# UART_USB.net
KiCad netlist of a schematic drawn in Altium Designer
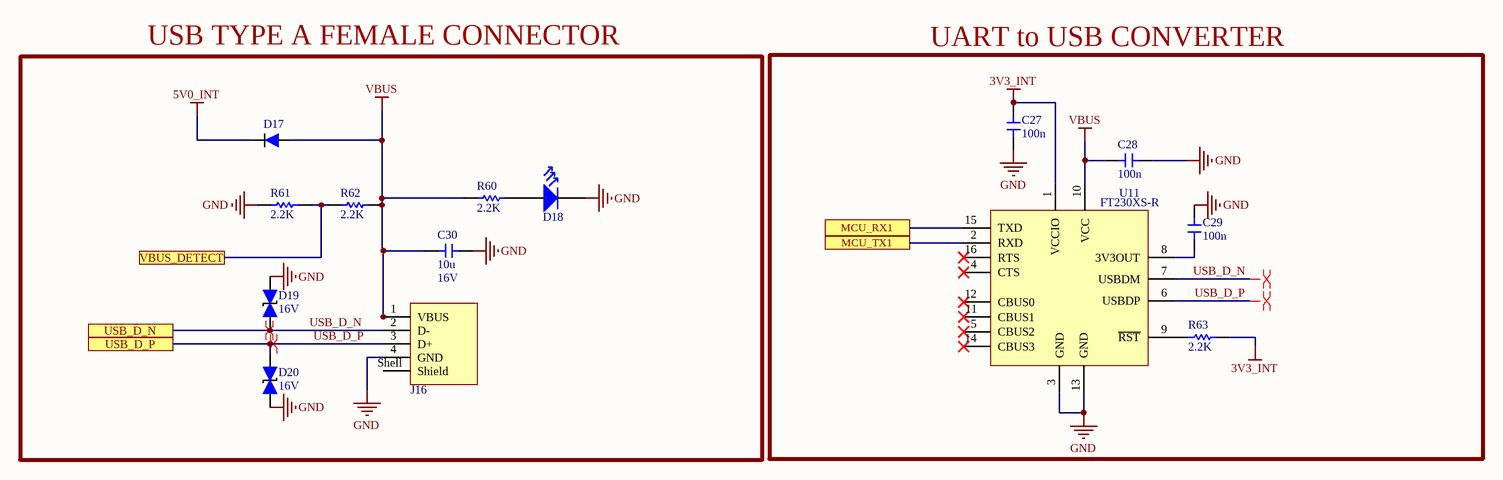
[diagram p0: UART_USB.SchDoc]

(export (version "E")
  (design (tool "Eeschema 10.0.6"))
  (components
    (comp (ref "C27")
      (value "100n")
      (footprint "CAP_0402_CER")
      (description "Generic")
      (fields (field (name "PART NUMBER") "CL05B104KP5NNNC") (field (name "VOLTAGE") "10V"))
      (libsource (lib "MareLux24Lib") (part "CAP_GEN_CER"))
    )
    (comp (ref "C28")
      (value "100n")
      (footprint "CAP_0402_CER")
      (description "Generic")
      (fields (field (name "PART NUMBER") "CL05B104KP5NNNC") (field (name "VOLTAGE") "10V"))
      (libsource (lib "MareLux24Lib") (part "CAP_GEN_CER"))
    )
    (comp (ref "C29")
      (value "100n")
      (footprint "CAP_0402_CER")
      (description "Generic")
      (fields (field (name "PART NUMBER") "CL05B104KP5NNNC") (field (name "VOLTAGE") "10V"))
      (libsource (lib "MareLux24Lib") (part "CAP_GEN_CER"))
    )
    (comp (ref "C30")
      (value "10u")
      (footprint "CAP_0805_CER")
      (description "Generic")
      (fields (field (name "PART NUMBER") "CL21A106KOQNNNE") (field (name "VOLTAGE") "16V"))
      (libsource (lib "MareLux24Lib") (part "CAP_GEN_CER"))
    )
    (comp (ref "D17")
      (value "BAT42WS-E3-08")
      (footprint "SOD323F")
      (description "DIODE SCHOTTKY 30V 200MA")
      (fields (field (name "VOLTAGE") "30V"))
      (libsource (lib "MareLux24Lib") (part "BAT42WS-E3-08"))
    )
    (comp (ref "D18")
      (value "*")
      (footprint "LED_0805_SMD")
      (libsource (lib "MareLux24Lib") (part "LED_GEN"))
    )
    (comp (ref "D19")
      (value "16V")
      (footprint "SOD-123F")
      (description "Unidirectional TVS DIODE 200W 16V-17.8V SOD-123")
      (fields (field (name "PART NUMBER") "SMF16CA") (field (name "VOLTAGE") "17.8V"))
      (libsource (lib "MareLux24Lib") (part "SMF16CA"))
    )
    (comp (ref "D20")
      (value "16V")
      (footprint "SOD-123F")
      (description "Unidirectional TVS DIODE 200W 16V-17.8V SOD-123")
      (fields (field (name "PART NUMBER") "SMF16CA") (field (name "VOLTAGE") "17.8V"))
      (libsource (lib "MareLux24Lib") (part "SMF16CA"))
    )
    (comp (ref "J16")
      (value "UJ2-BH-1-TH")
      (footprint "61400416021")
      (description "WR-COM USB 2.0 Type A Horizontal")
      (fields
        (field (name "MANUFACTURER PART NUMBER") "61400416021")
        (field (name "MANUFACTURER") "Wurth Elektronik")
      )
      (libsource (lib "Altium_WR-USB_rev22b") (part "61400416021"))
    )
    (comp (ref "R60")
      (value "2.2K")
      (footprint "RES_0402_SMD")
      (description "Generic Chip Res")
      (fields (field (name "PART NUMBER") "RMCF0402JT2K20"))
      (libsource (lib "MareLux24Lib") (part "RES_GEN_SMD"))
    )
    (comp (ref "R61")
      (value "2.2K")
      (footprint "RES_0402_SMD")
      (description "Generic Chip Res")
      (fields (field (name "PART NUMBER") "RMCF0402JT2K20"))
      (libsource (lib "MareLux24Lib") (part "RES_GEN_SMD"))
    )
    (comp (ref "R62")
      (value "2.2K")
      (footprint "RES_0402_SMD")
      (description "Generic Chip Res")
      (fields (field (name "PART NUMBER") "RMCF0402JT2K20"))
      (libsource (lib "MareLux24Lib") (part "RES_GEN_SMD"))
    )
    (comp (ref "R63")
      (value "2.2K")
      (footprint "RES_0402_SMD")
      (description "Generic Chip Res")
      (fields (field (name "PART NUMBER") "RMCF0402JT2K20"))
      (libsource (lib "MareLux24Lib") (part "RES_GEN_SMD"))
    )
    (comp (ref "U11")
      (value "FT230XS-R")
      (footprint "16-SSOP")
      (description "IC USB SERIAL BASIC UART 16SSOP")
      (libsource (lib "MareLux24Lib") (part "FT230XS-R"))
    )
  )
  (nets
    (net (code "1") (name "/MCU_RX1") (class "Default")
      (node (ref "U11") (pin "15") (pinfunction "TXD_15") (pintype "passive"))
    )
    (net (code "2") (name "/MCU_TX1") (class "Default")
      (node (ref "U11") (pin "2") (pinfunction "RXD_2") (pintype "passive"))
    )
    (net (code "3") (name "/USB_D_N") (class "Default")
      (node (ref "D19") (pin "2") (pinfunction "A_2") (pintype "passive"))
      (node (ref "J16") (pin "2") (pinfunction "D-_2") (pintype "passive"))
      (node (ref "U11") (pin "7") (pinfunction "USBDM_7") (pintype "passive"))
    )
    (net (code "4") (name "/USB_D_P") (class "Default")
      (node (ref "D20") (pin "1") (pinfunction "C_1") (pintype "passive"))
      (node (ref "J16") (pin "3") (pinfunction "D+_3") (pintype "passive"))
      (node (ref "U11") (pin "6") (pinfunction "USBDP_6") (pintype "passive"))
    )
    (net (code "5") (name "/VBUS_DETECT") (class "Default")
      (node (ref "R61") (pin "2") (pinfunction "2_2") (pintype "passive"))
      (node (ref "R62") (pin "1") (pinfunction "1_1") (pintype "passive"))
    )
    (net (code "6") (name "3V3_INT") (class "Default")
      (node (ref "C27") (pin "1") (pinfunction "1_1") (pintype "passive"))
      (node (ref "R63") (pin "2") (pinfunction "2_2") (pintype "passive"))
      (node (ref "U11") (pin "1") (pinfunction "VCCIO_1") (pintype "power_in"))
    )
    (net (code "7") (name "5V0_INT") (class "Default")
      (node (ref "D17") (pin "1") (pinfunction "C_1") (pintype "passive"))
    )
    (net (code "8") (name "GND") (class "Default")
      (node (ref "C27") (pin "2") (pinfunction "2_2") (pintype "passive"))
      (node (ref "C28") (pin "1") (pinfunction "1_1") (pintype "passive"))
      (node (ref "C29") (pin "1") (pinfunction "1_1") (pintype "passive"))
      (node (ref "C30") (pin "1") (pinfunction "1_1") (pintype "passive"))
      (node (ref "D18") (pin "C") (pinfunction "C_C") (pintype "passive"))
      (node (ref "D19") (pin "1") (pinfunction "C_1") (pintype "passive"))
      (node (ref "D20") (pin "2") (pinfunction "A_2") (pintype "passive"))
      (node (ref "J16") (pin "4") (pinfunction "GND_4") (pintype "passive"))
      (node (ref "R61") (pin "1") (pinfunction "1_1") (pintype "passive"))
      (node (ref "U11") (pin "13") (pinfunction "GND_13") (pintype "power_in"))
      (node (ref "U11") (pin "3") (pinfunction "GND_3") (pintype "power_in"))
    )
    (net (code "9") (name "Net-(D18-PadA)") (class "Default")
      (node (ref "D18") (pin "A") (pinfunction "A_A") (pintype "passive"))
      (node (ref "R60") (pin "2") (pinfunction "2_2") (pintype "passive"))
    )
    (net (code "10") (name "Net-(U11-3V3OUT)") (class "Default")
      (node (ref "C29") (pin "2") (pinfunction "2_2") (pintype "passive"))
      (node (ref "U11") (pin "8") (pinfunction "3V3OUT_8") (pintype "passive"))
    )
    (net (code "11") (name "Net-(U11-~{RST})") (class "Default")
      (node (ref "R63") (pin "1") (pinfunction "1_1") (pintype "passive"))
      (node (ref "U11") (pin "9") (pinfunction "~{RST}_9") (pintype "passive"))
    )
    (net (code "12") (name "VBUS") (class "Default")
      (node (ref "C28") (pin "2") (pinfunction "2_2") (pintype "passive"))
      (node (ref "C30") (pin "2") (pinfunction "2_2") (pintype "passive"))
      (node (ref "D17") (pin "2") (pinfunction "A_2") (pintype "passive"))
      (node (ref "J16") (pin "1") (pinfunction "VBUS_1") (pintype "passive"))
      (node (ref "R60") (pin "1") (pinfunction "1_1") (pintype "passive"))
      (node (ref "R62") (pin "2") (pinfunction "2_2") (pintype "passive"))
      (node (ref "U11") (pin "10") (pinfunction "VCC_10") (pintype "power_in"))
    )
    (net (code "13") (name "unconnected-(J16-Shield-PadShell)") (class "Default")
      (node (ref "J16") (pin "Shell") (pinfunction "Shield_Shell") (pintype "passive"))
    )
    (net (code "14") (name "unconnected-(U11-CBUS0-Pad12)") (class "Default")
      (node (ref "U11") (pin "12") (pinfunction "CBUS0_12") (pintype "passive+no_connect"))
    )
    (net (code "15") (name "unconnected-(U11-CBUS1-Pad11)") (class "Default")
      (node (ref "U11") (pin "11") (pinfunction "CBUS1_11") (pintype "passive+no_connect"))
    )
    (net (code "16") (name "unconnected-(U11-CBUS2-Pad5)") (class "Default")
      (node (ref "U11") (pin "5") (pinfunction "CBUS2_5") (pintype "passive+no_connect"))
    )
    (net (code "17") (name "unconnected-(U11-CBUS3-Pad14)") (class "Default")
      (node (ref "U11") (pin "14") (pinfunction "CBUS3_14") (pintype "passive+no_connect"))
    )
    (net (code "18") (name "unconnected-(U11-CTS-Pad4)") (class "Default")
      (node (ref "U11") (pin "4") (pinfunction "CTS_4") (pintype "passive+no_connect"))
    )
    (net (code "19") (name "unconnected-(U11-RTS-Pad16)") (class "Default")
      (node (ref "U11") (pin "16") (pinfunction "RTS_16") (pintype "passive+no_connect"))
    )
  )
)
